# Sheet1.net
KiCad netlist of a schematic drawn in Altium Designer
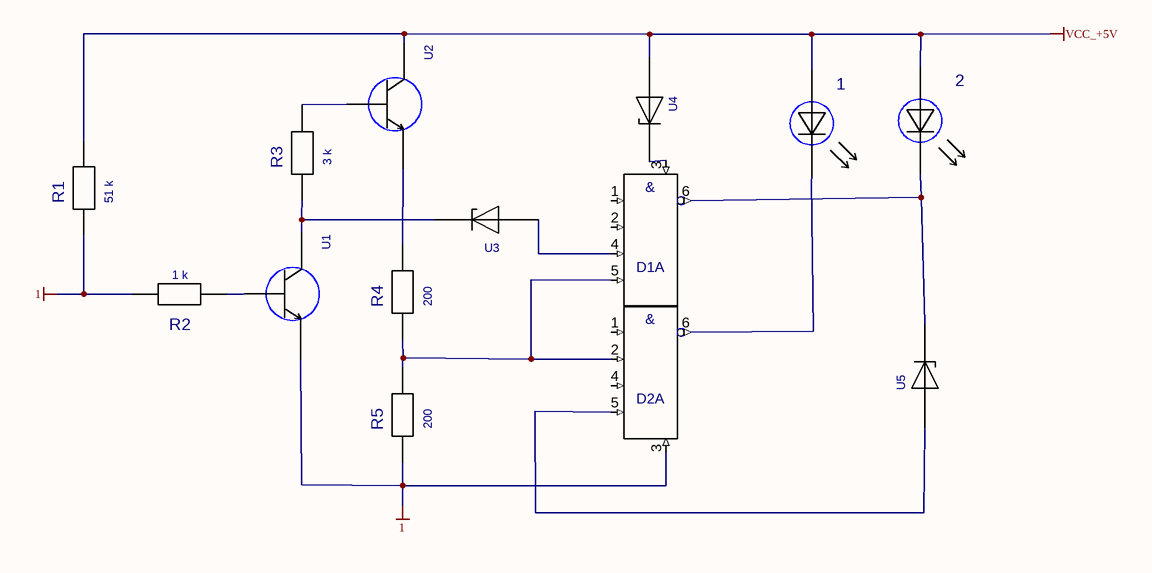
[diagram p0: Sheet1.SCHDOC]

(export (version "E")
  (design (tool "Eeschema 10.0.6"))
  (components
    (comp (ref "1")
      (value "DIODECORPUSMIC")
      (footprint "DIODE_CORPUS")
      (libsource (lib "*") (part "DIODECORPUSMIC"))
    )
    (comp (ref "2")
      (value "DIODECORPUSMIC")
      (footprint "DIODE_CORPUS")
      (libsource (lib "*") (part "DIODECORPUSMIC"))
    )
    (comp (ref "D1") (value "MICNEW") (footprint "DIP14") (libsource (lib "*") (part "MICNEW")))
    (comp (ref "D2") (value "MICNEW2") (footprint "DIP14") (libsource (lib "*") (part "MICNEW2")))
    (comp (ref "R1") (value "51 k") (footprint "RES") (description "RES") (libsource (lib "*") (part "RES")))
    (comp (ref "R2") (value "1 k") (footprint "RES") (description "RES") (libsource (lib "*") (part "RES")))
    (comp (ref "R3") (value "3 k") (footprint "RES") (description "RES") (libsource (lib "*") (part "RES")))
    (comp (ref "R4") (value "200") (footprint "RES") (description "RES") (libsource (lib "*") (part "RES")))
    (comp (ref "R5") (value "200") (footprint "RES") (description "RES") (libsource (lib "*") (part "RES")))
    (comp (ref "U1")
      (value "TRANSISTOR")
      (footprint "TRANSISTOR CORPUS")
      (libsource (lib "*") (part "TRANSISTOR"))
    )
    (comp (ref "U2")
      (value "TRANSISTOR")
      (footprint "TRANSISTOR CORPUS")
      (libsource (lib "*") (part "TRANSISTOR"))
    )
    (comp (ref "U3") (value "DIODE") (footprint "DIODE_CORPUS") (libsource (lib "*") (part "DIODE")))
    (comp (ref "U4") (value "DIODE") (footprint "DIODE_CORPUS") (libsource (lib "*") (part "DIODE")))
    (comp (ref "U5") (value "DIODE") (footprint "DIODE_CORPUS") (libsource (lib "*") (part "DIODE")))
  )
  (nets
    (net (code "1") (name "1") (class "Default")
      (node (ref "D2") (pin "3") (pinfunction "IN6_3") (pintype "input"))
      (node (ref "R1") (pin "1") (pinfunction "1_1") (pintype "passive"))
      (node (ref "R2") (pin "2") (pinfunction "2_2") (pintype "passive"))
      (node (ref "R5") (pin "1") (pinfunction "1_1") (pintype "passive"))
      (node (ref "U1") (pin "C") (pinfunction "0_C") (pintype "passive"))
    )
    (net (code "2") (name "GND") (class "Default")
      (node (ref "D1") (pin "7") (pinfunction "GND_7") (pintype "power_in"))
      (node (ref "D2") (pin "7") (pinfunction "GND_7") (pintype "power_in"))
    )
    (net (code "3") (name "Net-(1-A2)") (class "Default")
      (node (ref "1") (pin "2") (pinfunction "A2_2") (pintype "passive"))
      (node (ref "D2") (pin "6") (pinfunction "OUT_6") (pintype "output"))
    )
    (net (code "4") (name "Net-(2-A2)") (class "Default")
      (node (ref "2") (pin "2") (pinfunction "A2_2") (pintype "passive"))
      (node (ref "D1") (pin "6") (pinfunction "OUT_6") (pintype "output"))
      (node (ref "U5") (pin "1") (pinfunction "0_1") (pintype "passive"))
    )
    (net (code "5") (name "Net-(D1A-IN3)") (class "Default")
      (node (ref "D1") (pin "4") (pinfunction "IN3_4") (pintype "input"))
      (node (ref "U3") (pin "2") (pinfunction "0_2") (pintype "passive"))
    )
    (net (code "6") (name "Net-(D1A-IN4)") (class "Default")
      (node (ref "D1") (pin "5") (pinfunction "IN4_5") (pintype "input"))
      (node (ref "D2") (pin "2") (pinfunction "IN1_2") (pintype "input"))
      (node (ref "R4") (pin "1") (pinfunction "1_1") (pintype "passive"))
      (node (ref "R5") (pin "2") (pinfunction "2_2") (pintype "passive"))
    )
    (net (code "7") (name "Net-(D1A-IN6)") (class "Default")
      (node (ref "D1") (pin "3") (pinfunction "IN6_3") (pintype "input"))
      (node (ref "U4") (pin "1") (pinfunction "0_1") (pintype "passive"))
    )
    (net (code "8") (name "Net-(D2A-IN4)") (class "Default")
      (node (ref "D2") (pin "5") (pinfunction "IN4_5") (pintype "input"))
      (node (ref "U5") (pin "2") (pinfunction "0_2") (pintype "passive"))
    )
    (net (code "9") (name "Net-(R2-Pad1)") (class "Default")
      (node (ref "R2") (pin "1") (pinfunction "1_1") (pintype "passive"))
      (node (ref "U1") (pin "B") (pinfunction "B_B") (pintype "passive"))
    )
    (net (code "10") (name "Net-(R3-Pad1)") (class "Default")
      (node (ref "R3") (pin "1") (pinfunction "1_1") (pintype "passive"))
      (node (ref "U1") (pin "E") (pinfunction "E_E") (pintype "passive"))
      (node (ref "U3") (pin "1") (pinfunction "0_1") (pintype "passive"))
    )
    (net (code "11") (name "Net-(R3-Pad2)") (class "Default")
      (node (ref "R3") (pin "2") (pinfunction "2_2") (pintype "passive"))
      (node (ref "U2") (pin "B") (pinfunction "B_B") (pintype "passive"))
    )
    (net (code "12") (name "Net-(U2-0)") (class "Default")
      (node (ref "R4") (pin "2") (pinfunction "2_2") (pintype "passive"))
      (node (ref "U2") (pin "C") (pinfunction "0_C") (pintype "passive"))
    )
    (net (code "13") (name "VCC") (class "Default")
      (node (ref "D1") (pin "14") (pinfunction "VCC_14") (pintype "power_in"))
      (node (ref "D2") (pin "14") (pinfunction "VCC_14") (pintype "power_in"))
    )
    (net (code "14") (name "VCC_+5V") (class "Default")
      (node (ref "1") (pin "1") (pinfunction "A1_1") (pintype "passive"))
      (node (ref "2") (pin "1") (pinfunction "A1_1") (pintype "passive"))
      (node (ref "R1") (pin "2") (pinfunction "2_2") (pintype "passive"))
      (node (ref "U2") (pin "E") (pinfunction "E_E") (pintype "passive"))
      (node (ref "U4") (pin "2") (pinfunction "0_2") (pintype "passive"))
    )
    (net (code "15") (name "unconnected-(D1A-IN0-Pad1)") (class "Default")
      (node (ref "D1") (pin "1") (pinfunction "IN0_1") (pintype "input"))
    )
    (net (code "16") (name "unconnected-(D1A-IN1-Pad2)") (class "Default")
      (node (ref "D1") (pin "2") (pinfunction "IN1_2") (pintype "input"))
    )
    (net (code "17") (name "unconnected-(D2A-IN0-Pad1)") (class "Default")
      (node (ref "D2") (pin "1") (pinfunction "IN0_1") (pintype "input"))
    )
    (net (code "18") (name "unconnected-(D2A-IN3-Pad4)") (class "Default")
      (node (ref "D2") (pin "4") (pinfunction "IN3_4") (pintype "input"))
    )
  )
)
